# shutdown_circuit.net
KiCad netlist of a schematic drawn in Altium Designer
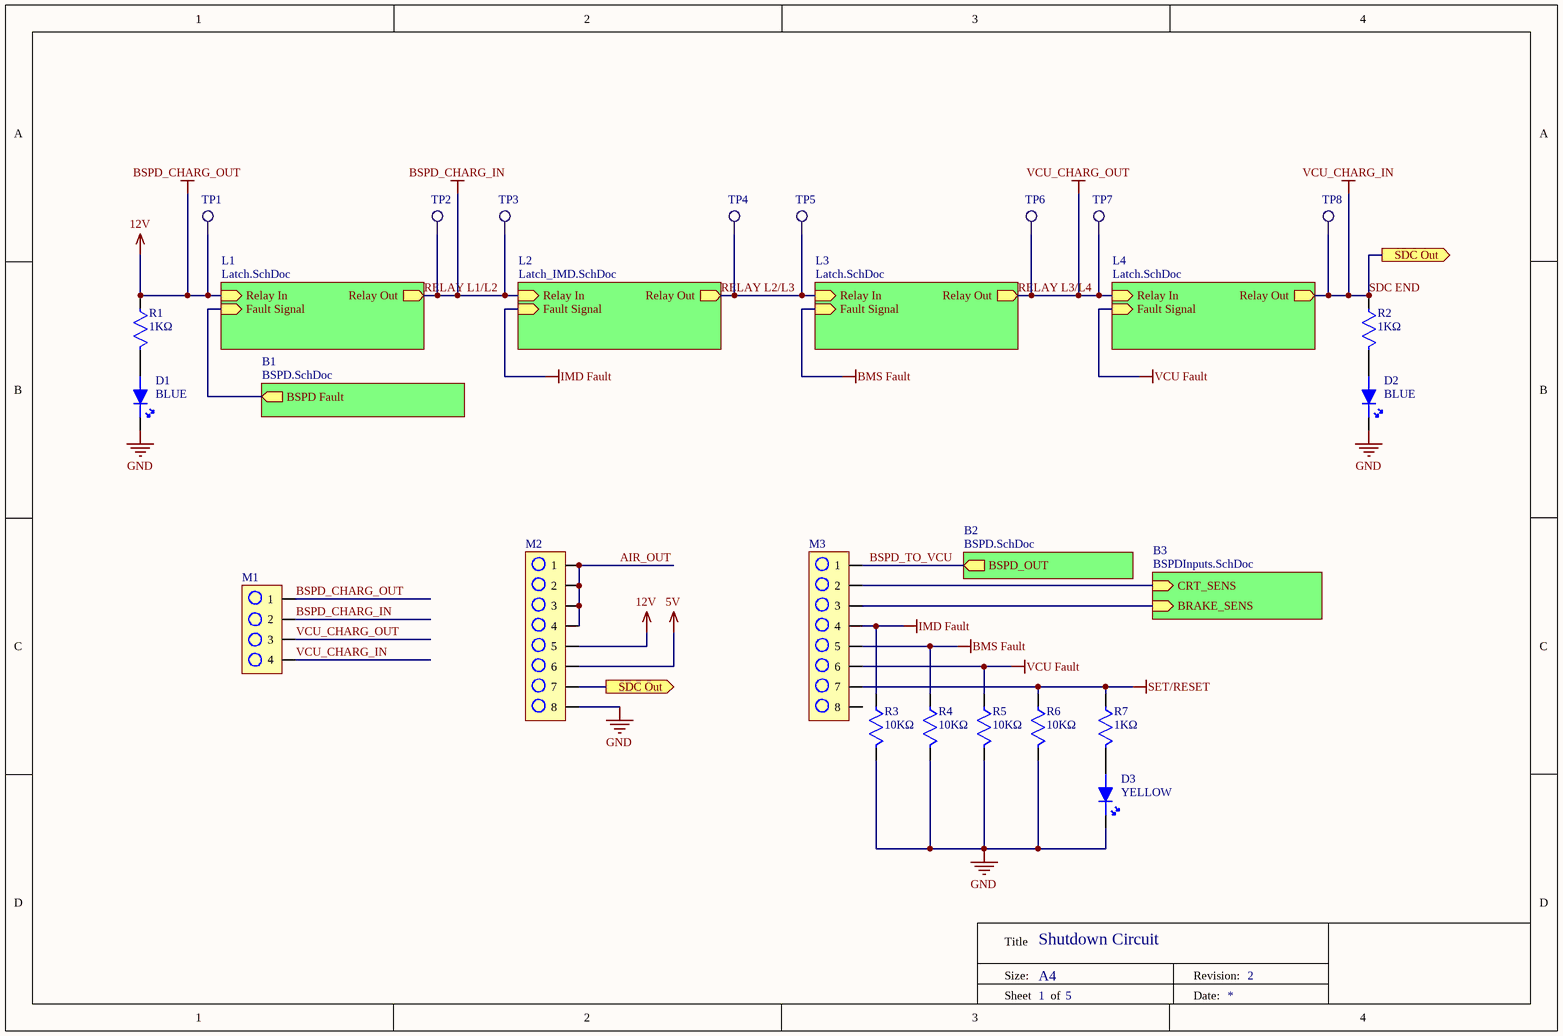
[diagram p0: shutdown_circuit.SchDoc]

(export (version "E")
  (design (tool "Eeschema 10.0.6"))
  (components
    (comp (ref "D1")
      (value "BLUE")
      (footprint "LED 0603")
      (description "LED BLUE CLEAR CHIP SMD")
      (fields
        (field (name "MANUFACTURER") "Vishay Lite-On")
        (field (name "MANUFACTURER PART NUMBER") "LTST-C191TBKT-5A")
      )
      (libsource (lib "sdc_prech_schlib") (part "LTST-C191TBKT-5A"))
    )
    (comp (ref "D2")
      (value "BLUE")
      (footprint "LED 0603")
      (description "LED BLUE CLEAR CHIP SMD")
      (fields
        (field (name "MANUFACTURER") "Vishay Lite-On")
        (field (name "MANUFACTURER PART NUMBER") "LTST-C191TBKT-5A")
      )
      (libsource (lib "sdc_prech_schlib") (part "LTST-C191TBKT-5A"))
    )
    (comp (ref "D3")
      (value "YELLOW")
      (footprint "LED 0603")
      (description "LED YELLOW CLEAR SMD")
      (fields
        (field (name "MANUFACTURER") "Vishay Lite-On")
        (field (name "MANUFACTURER PART NUMBER") "LTST-C191KSKT")
      )
      (libsource (lib "sdc_prech_schlib") (part "LTST-C191KSKT"))
    )
    (comp (ref "M1")
      (value "0436500428")
      (footprint "4-PIN MOLEX")
      (description "Conn Power HDR 4 POS 3mm Solder ST Thru-Hole 4 Terminal 1 Port Micro-Fit 3.0™ Tray")
      (fields (field (name "MANUFACTURER") "Molex"))
      (libsource (lib "sdc_prech_schlib") (part "0436500428"))
    )
    (comp (ref "M2")
      (value "2068320802")
      (footprint "4X2-PIN MOLEX")
      (description "CONN HEADER 4X2 POS, 3.00mm Pitch")
      (fields (field (name "COPYRIGHT") "Copyright (C) 2018 Accelerated Designs. All rights reserved"))
      (libsource (lib "sdc_prech_schlib") (part "2068320802"))
    )
    (comp (ref "M3")
      (value "2068320802")
      (footprint "4X2-PIN MOLEX")
      (description "CONN HEADER 4X2 POS, 3.00mm Pitch")
      (fields (field (name "COPYRIGHT") "Copyright (C) 2018 Accelerated Designs. All rights reserved"))
      (libsource (lib "sdc_prech_schlib") (part "2068320802"))
    )
    (comp (ref "R1")
      (value "1KΩ")
      (footprint "RESISTOR 0603")
      (description "RES SMD 1K OHM 1% 1/10W 0603")
      (fields
        (field (name "MANUFACTURER") "Vishay Dale")
        (field (name "MANUFACTURER PART NUMBER") "CRCW06031K00FKEA")
      )
      (libsource (lib "sdc_prech_schlib") (part "CRCW06031K00FKEA"))
    )
    (comp (ref "R2")
      (value "1KΩ")
      (footprint "RESISTOR 0603")
      (description "RES SMD 1K OHM 1% 1/10W 0603")
      (fields
        (field (name "MANUFACTURER") "Vishay Dale")
        (field (name "MANUFACTURER PART NUMBER") "CRCW06031K00FKEA")
      )
      (libsource (lib "sdc_prech_schlib") (part "CRCW06031K00FKEA"))
    )
    (comp (ref "R3")
      (value "10KΩ")
      (footprint "RESISTOR 0603")
      (description "RES SMD 10K OHM 1% 1/10W 0603")
      (fields
        (field (name "MANUFACTURER") "Vishay")
        (field (name "MANUFACTURER PART NUMBER") "CRCW060310K0FKEA")
      )
      (libsource (lib "sdc_prech_schlib") (part "CRCW060310K0FKEA"))
    )
    (comp (ref "R4")
      (value "10KΩ")
      (footprint "RESISTOR 0603")
      (description "RES SMD 10K OHM 1% 1/10W 0603")
      (fields
        (field (name "MANUFACTURER") "Vishay")
        (field (name "MANUFACTURER PART NUMBER") "CRCW060310K0FKEA")
      )
      (libsource (lib "sdc_prech_schlib") (part "CRCW060310K0FKEA"))
    )
    (comp (ref "R5")
      (value "10KΩ")
      (footprint "RESISTOR 0603")
      (description "RES SMD 10K OHM 1% 1/10W 0603")
      (fields
        (field (name "MANUFACTURER") "Vishay")
        (field (name "MANUFACTURER PART NUMBER") "CRCW060310K0FKEA")
      )
      (libsource (lib "sdc_prech_schlib") (part "CRCW060310K0FKEA"))
    )
    (comp (ref "R6")
      (value "10KΩ")
      (footprint "RESISTOR 0603")
      (description "RES SMD 10K OHM 1% 1/10W 0603")
      (fields
        (field (name "MANUFACTURER") "Vishay")
        (field (name "MANUFACTURER PART NUMBER") "CRCW060310K0FKEA")
      )
      (libsource (lib "sdc_prech_schlib") (part "CRCW060310K0FKEA"))
    )
    (comp (ref "R7")
      (value "1KΩ")
      (footprint "RESISTOR 0603")
      (description "RES SMD 1K OHM 1% 1/10W 0603")
      (fields
        (field (name "MANUFACTURER") "Vishay Dale")
        (field (name "MANUFACTURER PART NUMBER") "CRCW06031K00FKEA")
      )
      (libsource (lib "sdc_prech_schlib") (part "CRCW06031K00FKEA"))
    )
    (comp (ref "TP1")
      (value "Testpoint2")
      (footprint "TP2")
      (description "Single layer pad TP")
      (libsource (lib "Misc") (part "Testpoint2"))
    )
    (comp (ref "TP2")
      (value "Testpoint2")
      (footprint "TP2")
      (description "Single layer pad TP")
      (libsource (lib "Misc") (part "Testpoint2"))
    )
    (comp (ref "TP3")
      (value "Testpoint2")
      (footprint "TP2")
      (description "Single layer pad TP")
      (libsource (lib "Misc") (part "Testpoint2"))
    )
    (comp (ref "TP4")
      (value "Testpoint2")
      (footprint "TP2")
      (description "Single layer pad TP")
      (libsource (lib "Misc") (part "Testpoint2"))
    )
    (comp (ref "TP5")
      (value "Testpoint2")
      (footprint "TP2")
      (description "Single layer pad TP")
      (libsource (lib "Misc") (part "Testpoint2"))
    )
    (comp (ref "TP6")
      (value "Testpoint2")
      (footprint "TP2")
      (description "Single layer pad TP")
      (libsource (lib "Misc") (part "Testpoint2"))
    )
    (comp (ref "TP7")
      (value "Testpoint2")
      (footprint "TP2")
      (description "Single layer pad TP")
      (libsource (lib "Misc") (part "Testpoint2"))
    )
    (comp (ref "TP8")
      (value "Testpoint2")
      (footprint "TP2")
      (description "Single layer pad TP")
      (libsource (lib "Misc") (part "Testpoint2"))
    )
  )
  (nets
    (net (code "1") (name "/AIR_OUT") (class "Default")
      (node (ref "M2") (pin "1") (pinfunction "1_1") (pintype "passive"))
      (node (ref "M2") (pin "2") (pinfunction "2_2") (pintype "passive"))
      (node (ref "M2") (pin "3") (pinfunction "3_3") (pintype "passive"))
      (node (ref "M2") (pin "4") (pinfunction "4_4") (pintype "passive"))
    )
    (net (code "2") (name "/BRAKE_SENS") (class "Default")
      (node (ref "M3") (pin "3") (pinfunction "3_3") (pintype "passive"))
    )
    (net (code "4") (name "/BSPD_TO_VCU") (class "Default")
      (node (ref "M3") (pin "1") (pinfunction "1_1") (pintype "passive"))
    )
    (net (code "5") (name "/CRT_SENS") (class "Default")
      (node (ref "M3") (pin "2") (pinfunction "2_2") (pintype "passive"))
    )
    (net (code "6") (name "/RELAY L2{slash}L3") (class "Default")
      (node (ref "TP4") (pin "1") (pinfunction "1_1") (pintype "passive"))
      (node (ref "TP5") (pin "1") (pinfunction "1_1") (pintype "passive"))
    )
    (net (code "7") (name "5V") (class "Default")
      (node (ref "M2") (pin "6") (pinfunction "6_6") (pintype "passive"))
    )
    (net (code "8") (name "12V") (class "Default")
      (node (ref "M1") (pin "1") (pinfunction "1_1") (pintype "passive"))
      (node (ref "M2") (pin "5") (pinfunction "5_5") (pintype "passive"))
      (node (ref "R1") (pin "1") (pinfunction "1_1") (pintype "passive"))
      (node (ref "TP1") (pin "1") (pinfunction "1_1") (pintype "passive"))
    )
    (net (code "9") (name "BMS Fault") (class "Default")
      (node (ref "M3") (pin "5") (pinfunction "5_5") (pintype "passive"))
      (node (ref "R4") (pin "1") (pinfunction "1_1") (pintype "passive"))
    )
    (net (code "10") (name "BSPD_CHARG_IN") (class "Default")
      (node (ref "M1") (pin "2") (pinfunction "2_2") (pintype "passive"))
      (node (ref "TP2") (pin "1") (pinfunction "1_1") (pintype "passive"))
      (node (ref "TP3") (pin "1") (pinfunction "1_1") (pintype "passive"))
    )
    (net (code "11") (name "GND") (class "Default")
      (node (ref "D1") (pin "2") (pinfunction "2_2") (pintype "passive"))
      (node (ref "D2") (pin "2") (pinfunction "2_2") (pintype "passive"))
      (node (ref "D3") (pin "2") (pinfunction "2_2") (pintype "passive"))
      (node (ref "M2") (pin "8") (pinfunction "8_8") (pintype "passive"))
      (node (ref "R3") (pin "2") (pinfunction "2_2") (pintype "passive"))
      (node (ref "R4") (pin "2") (pinfunction "2_2") (pintype "passive"))
      (node (ref "R5") (pin "2") (pinfunction "2_2") (pintype "passive"))
      (node (ref "R6") (pin "2") (pinfunction "2_2") (pintype "passive"))
    )
    (net (code "12") (name "IMD Fault") (class "Default")
      (node (ref "M3") (pin "4") (pinfunction "4_4") (pintype "passive"))
      (node (ref "R3") (pin "1") (pinfunction "1_1") (pintype "passive"))
    )
    (net (code "13") (name "Net-(D1-Pad1)") (class "Default")
      (node (ref "D1") (pin "1") (pinfunction "1_1") (pintype "passive"))
      (node (ref "R1") (pin "2") (pinfunction "2_2") (pintype "passive"))
    )
    (net (code "14") (name "Net-(D2-Pad1)") (class "Default")
      (node (ref "D2") (pin "1") (pinfunction "1_1") (pintype "passive"))
      (node (ref "R2") (pin "2") (pinfunction "2_2") (pintype "passive"))
    )
    (net (code "15") (name "Net-(D3-Pad1)") (class "Default")
      (node (ref "D3") (pin "1") (pinfunction "1_1") (pintype "passive"))
      (node (ref "R7") (pin "2") (pinfunction "2_2") (pintype "passive"))
    )
    (net (code "16") (name "SET{slash}RESET") (class "Default")
      (node (ref "M3") (pin "7") (pinfunction "7_7") (pintype "passive"))
      (node (ref "R6") (pin "1") (pinfunction "1_1") (pintype "passive"))
      (node (ref "R7") (pin "1") (pinfunction "1_1") (pintype "passive"))
    )
    (net (code "17") (name "VCU Fault") (class "Default")
      (node (ref "M3") (pin "6") (pinfunction "6_6") (pintype "passive"))
      (node (ref "R5") (pin "1") (pinfunction "1_1") (pintype "passive"))
    )
    (net (code "18") (name "VCU_CHARG_IN") (class "Default")
      (node (ref "M1") (pin "4") (pinfunction "4_4") (pintype "passive"))
      (node (ref "M2") (pin "7") (pinfunction "7_7") (pintype "passive"))
      (node (ref "R2") (pin "1") (pinfunction "1_1") (pintype "passive"))
      (node (ref "TP8") (pin "1") (pinfunction "1_1") (pintype "passive"))
    )
    (net (code "19") (name "VCU_CHARG_OUT") (class "Default")
      (node (ref "M1") (pin "3") (pinfunction "3_3") (pintype "passive"))
      (node (ref "TP6") (pin "1") (pinfunction "1_1") (pintype "passive"))
      (node (ref "TP7") (pin "1") (pinfunction "1_1") (pintype "passive"))
    )
    (net (code "20") (name "unconnected-(M3-Pad8)") (class "Default")
      (node (ref "M3") (pin "8") (pinfunction "8_8") (pintype "passive"))
    )
  )
)
